# Atmega328p_Custom_Board.net
KiCad netlist of a schematic drawn in EasyEDA
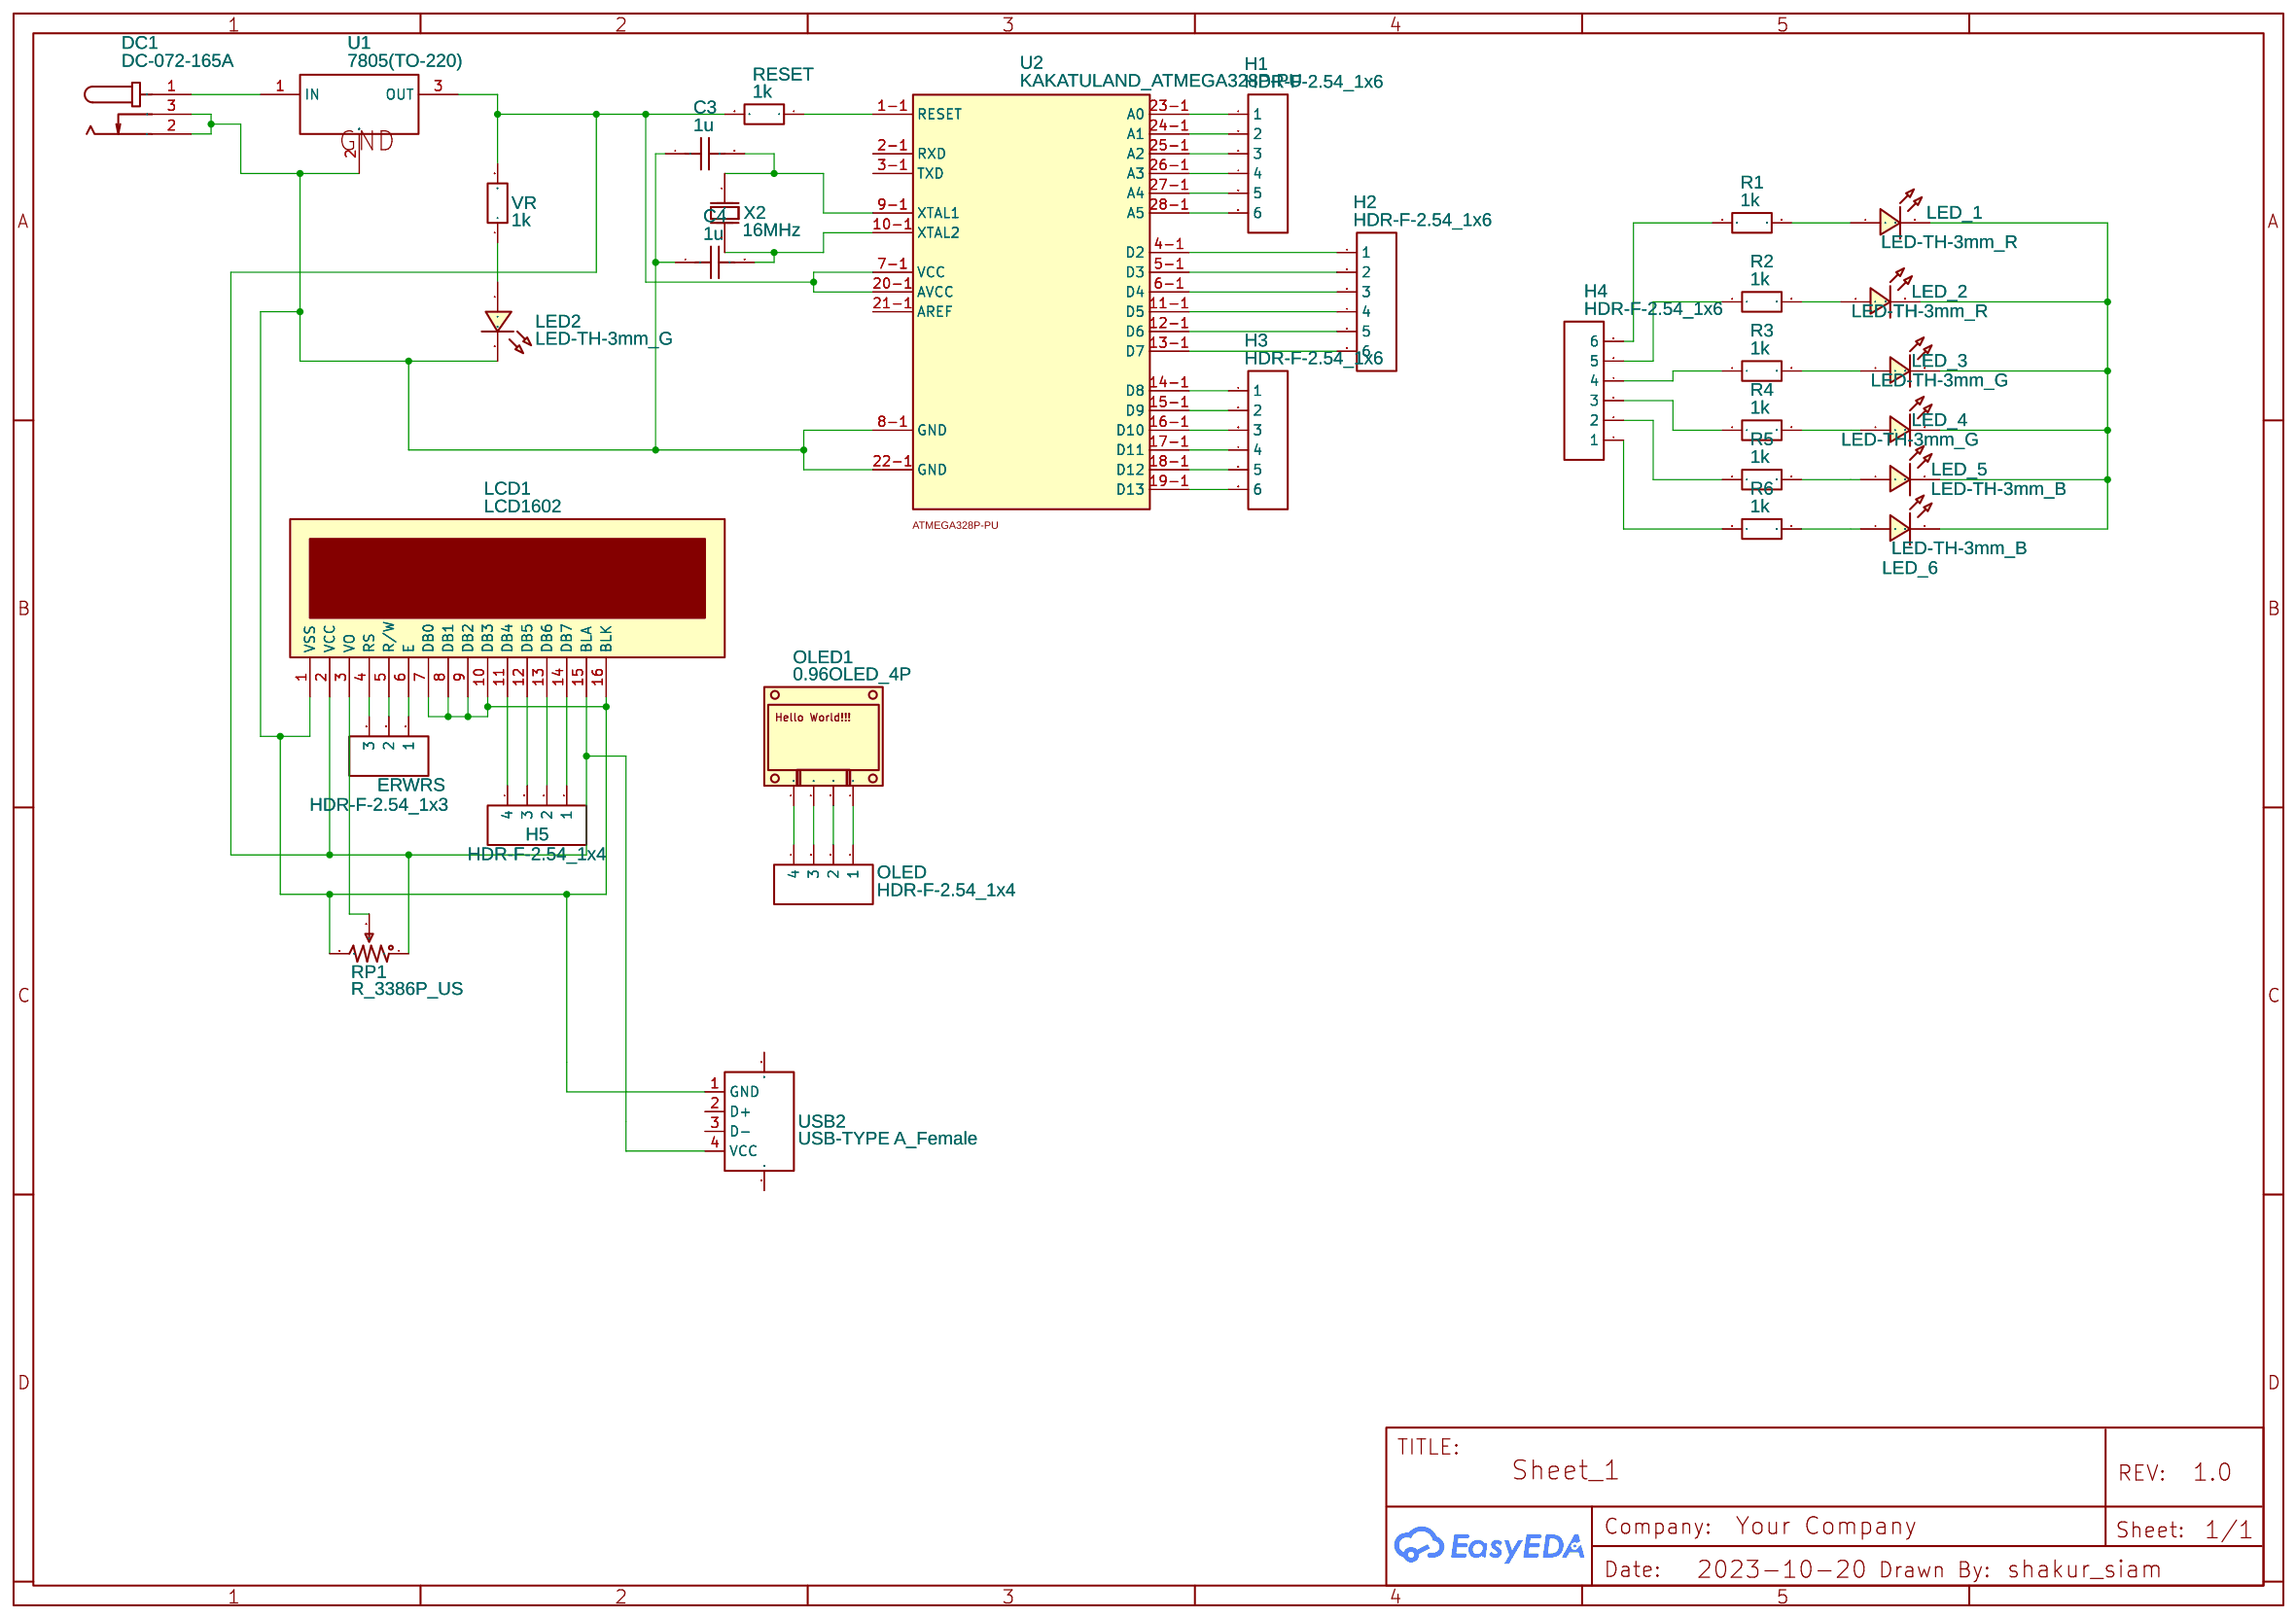
[diagram p0: schematic sheet]

(export (version "E")
  (design (tool "Eeschema 10.0.6"))
  (components
    (comp (ref "C3") (value "1u") (libsource (lib "") (part "C_RAD-0.2_US")))
    (comp (ref "C4") (value "1u") (libsource (lib "") (part "C_RAD-0.2_US")))
    (comp (ref "DC1")
      (value "DC-072-165A")
      (fields (field (name "Manufacturer") "HRO"))
      (libsource (lib "") (part "DC-072-165A"))
    )
    (comp (ref "ERWRS") (value "HDR-F-2.54_1x3") (libsource (lib "") (part "HDR-F-2.54_1x3")))
    (comp (ref "H1") (value "HDR-F-2.54_1x6") (libsource (lib "") (part "HDR-F-2.54_1x6")))
    (comp (ref "H2") (value "HDR-F-2.54_1x6") (libsource (lib "") (part "HDR-F-2.54_1x6")))
    (comp (ref "H3") (value "HDR-F-2.54_1x6") (libsource (lib "") (part "HDR-F-2.54_1x6")))
    (comp (ref "H4") (value "HDR-F-2.54_1x6") (libsource (lib "") (part "HDR-F-2.54_1x6_1")))
    (comp (ref "H5") (value "HDR-F-2.54_1x4") (libsource (lib "") (part "HDR-F-2.54_1x4_1")))
    (comp (ref "LCD1")
      (value "LCD1602")
      (fields
        (field (name "Manufacturer Part") "LCM1602K-NSW-BBW")
        (field (name "Manufacturer") "LONTECH(厦门龙特)")
      )
      (libsource (lib "") (part "LCD1602"))
    )
    (comp (ref "LED2")
      (value "LED-TH-3mm_G")
      (fields
        (field (name "Manufacturer Part") "204-10SYGD/S530-E3")
        (field (name "Manufacturer") "EVERLIGHT(台湾亿光)")
      )
      (libsource (lib "") (part "LED-TH-3mm_G_1"))
    )
    (comp (ref "LED_1")
      (value "LED-TH-3mm_R")
      (fields
        (field (name "Manufacturer Part") "204-10SDRD/S530-A3-L")
        (field (name "Manufacturer") "EVERLIGHT(台湾亿光)")
      )
      (libsource (lib "") (part "LED-TH-3mm_R"))
    )
    (comp (ref "LED_2")
      (value "LED-TH-3mm_R")
      (fields
        (field (name "Manufacturer Part") "204-10SDRD/S530-A3-L")
        (field (name "Manufacturer") "EVERLIGHT(台湾亿光)")
      )
      (libsource (lib "") (part "LED-TH-3mm_R"))
    )
    (comp (ref "LED_3")
      (value "LED-TH-3mm_G")
      (fields
        (field (name "Manufacturer Part") "204-10SYGD/S530-E3")
        (field (name "Manufacturer") "EVERLIGHT(台湾亿光)")
      )
      (libsource (lib "") (part "LED-TH-3mm_G"))
    )
    (comp (ref "LED_4")
      (value "LED-TH-3mm_G")
      (fields
        (field (name "Manufacturer Part") "204-10SYGD/S530-E3")
        (field (name "Manufacturer") "EVERLIGHT(台湾亿光)")
      )
      (libsource (lib "") (part "LED-TH-3mm_G"))
    )
    (comp (ref "LED_5")
      (value "LED-TH-3mm_B")
      (fields
        (field (name "Manufacturer Part") "204-10SUBC/S400-A4")
        (field (name "Manufacturer") "EVERLIGHT(台湾亿光)")
      )
      (libsource (lib "") (part "LED-TH-3mm_B"))
    )
    (comp (ref "LED_6")
      (value "LED-TH-3mm_B")
      (fields
        (field (name "Manufacturer Part") "204-10SUBC/S400-A4")
        (field (name "Manufacturer") "EVERLIGHT(台湾亿光)")
      )
      (libsource (lib "") (part "LED-TH-3mm_B"))
    )
    (comp (ref "OLED") (value "HDR-F-2.54_1x4") (libsource (lib "") (part "HDR-F-2.54_1x4")))
    (comp (ref "OLED1") (value "0.96OLED_4P") (libsource (lib "") (part "0.96OLED_4P")))
    (comp (ref "R1") (value "1k") (libsource (lib "") (part "R_0603_EU")))
    (comp (ref "R2") (value "1k") (libsource (lib "") (part "R_0603_EU")))
    (comp (ref "R3") (value "1k") (libsource (lib "") (part "R_0603_EU")))
    (comp (ref "R4") (value "1k") (libsource (lib "") (part "R_0603_EU")))
    (comp (ref "R5") (value "1k") (libsource (lib "") (part "R_0603_EU")))
    (comp (ref "R6") (value "1k") (libsource (lib "") (part "R_0603_EU")))
    (comp (ref "RESET") (value "1k") (libsource (lib "") (part "R_0603_EU_1")))
    (comp (ref "RP1") (value "R_3386P_US") (libsource (lib "") (part "R_3386P_US")))
    (comp (ref "U1")
      (value "7805(TO-220)")
      (fields
        (field (name "Manufacturer Part") "L7805CV-DG")
        (field (name "Manufacturer") "STMicroelectronics")
      )
      (libsource (lib "") (part "7805(TO-220)"))
    )
    (comp (ref "U2")
      (value "KAKATULAND_ATMEGA328P-PU")
      (libsource (lib "") (part "KAKATULAND_ATMEGA328P-PU"))
    )
    (comp (ref "USB2")
      (value "USB-TYPE A_Female")
      (fields (field (name "Manufacturer") "ValuePro"))
      (libsource (lib "") (part "USB-TYPE A_Female"))
    )
    (comp (ref "VR") (value "1k") (libsource (lib "") (part "R_0603_EU_2")))
    (comp (ref "X2") (value "16MHz") (libsource (lib "") (part "GM-CRYSTAL-16MHz")))
  )
  (nets
    (net (code "1") (name "Net-(H4-Pad1)") (class "Default")
      (node (ref "H4") (pin "1") (pinfunction "1_1") (pintype "input"))
      (node (ref "R6") (pin "1") (pinfunction "1_1") (pintype "unspecified"))
    )
    (net (code "2") (name "Net-(H4-Pad2)") (class "Default")
      (node (ref "H4") (pin "2") (pinfunction "2_2") (pintype "input"))
      (node (ref "R5") (pin "1") (pinfunction "1_1") (pintype "unspecified"))
    )
    (net (code "3") (name "Net-(H4-Pad3)") (class "Default")
      (node (ref "H4") (pin "3") (pinfunction "3_3") (pintype "input"))
      (node (ref "R4") (pin "1") (pinfunction "1_1") (pintype "unspecified"))
    )
    (net (code "4") (name "Net-(H4-Pad4)") (class "Default")
      (node (ref "H4") (pin "4") (pinfunction "4_4") (pintype "input"))
      (node (ref "R3") (pin "1") (pinfunction "1_1") (pintype "unspecified"))
    )
    (net (code "5") (name "Net-(H4-Pad5)") (class "Default")
      (node (ref "H4") (pin "5") (pinfunction "5_5") (pintype "input"))
      (node (ref "R2") (pin "1") (pinfunction "1_1") (pintype "unspecified"))
    )
    (net (code "6") (name "Net-(H4-Pad6)") (class "Default")
      (node (ref "H4") (pin "6") (pinfunction "6_6") (pintype "input"))
      (node (ref "R1") (pin "1") (pinfunction "1_1") (pintype "unspecified"))
    )
    (net (code "7") (name "Net-(LCD1-BLA)") (class "Default")
      (node (ref "LCD1") (pin "15") (pinfunction "BLA_15") (pintype "unspecified"))
      (node (ref "LCD1") (pin "2") (pinfunction "VCC_2") (pintype "unspecified"))
      (node (ref "RESET") (pin "2") (pinfunction "2_2") (pintype "unspecified"))
      (node (ref "RP1") (pin "1") (pinfunction "1_1") (pintype "unspecified"))
      (node (ref "U1") (pin "3") (pinfunction "OUT_3") (pintype "passive"))
      (node (ref "U2") (pin "20-1") (pinfunction "AVCC_20-1") (pintype "passive"))
      (node (ref "U2") (pin "7-1") (pinfunction "VCC_7-1") (pintype "passive"))
      (node (ref "USB2") (pin "4") (pinfunction "VCC_4") (pintype "input"))
      (node (ref "VR") (pin "2") (pinfunction "2_2") (pintype "unspecified"))
    )
    (net (code "8") (name "Net-(LCD1-BLK)") (class "Default")
      (node (ref "C3") (pin "1") (pinfunction "1_1") (pintype "unspecified"))
      (node (ref "C4") (pin "1") (pinfunction "1_1") (pintype "unspecified"))
      (node (ref "DC1") (pin "2") (pinfunction "2_2") (pintype "unspecified"))
      (node (ref "DC1") (pin "3") (pinfunction "3_3") (pintype "unspecified"))
      (node (ref "LCD1") (pin "1") (pinfunction "VSS_1") (pintype "unspecified"))
      (node (ref "LCD1") (pin "10") (pinfunction "DB3_10") (pintype "unspecified"))
      (node (ref "LCD1") (pin "16") (pinfunction "BLK_16") (pintype "unspecified"))
      (node (ref "LCD1") (pin "7") (pinfunction "DB0_7") (pintype "unspecified"))
      (node (ref "LCD1") (pin "8") (pinfunction "DB1_8") (pintype "unspecified"))
      (node (ref "LCD1") (pin "9") (pinfunction "DB2_9") (pintype "unspecified"))
      (node (ref "LED2") (pin "2") (pinfunction "2_2") (pintype "unspecified"))
      (node (ref "RP1") (pin "3") (pinfunction "3_3") (pintype "unspecified"))
      (node (ref "U1") (pin "2") (pinfunction "GND_2") (pintype "passive"))
      (node (ref "U2") (pin "22-1") (pinfunction "GND_22-1") (pintype "passive"))
      (node (ref "U2") (pin "8-1") (pinfunction "GND_8-1") (pintype "passive"))
      (node (ref "USB2") (pin "1") (pinfunction "GND_1") (pintype "input"))
    )
    (net (code "9") (name "Net-(LCD1-DB4)") (class "Default")
      (node (ref "H5") (pin "4") (pinfunction "4_4") (pintype "unspecified"))
      (node (ref "LCD1") (pin "11") (pinfunction "DB4_11") (pintype "unspecified"))
    )
    (net (code "10") (name "Net-(LCD1-DB5)") (class "Default")
      (node (ref "H5") (pin "3") (pinfunction "3_3") (pintype "unspecified"))
      (node (ref "LCD1") (pin "12") (pinfunction "DB5_12") (pintype "unspecified"))
    )
    (net (code "11") (name "Net-(LCD1-DB6)") (class "Default")
      (node (ref "H5") (pin "2") (pinfunction "2_2") (pintype "unspecified"))
      (node (ref "LCD1") (pin "13") (pinfunction "DB6_13") (pintype "unspecified"))
    )
    (net (code "12") (name "Net-(LCD1-DB7)") (class "Default")
      (node (ref "H5") (pin "1") (pinfunction "1_1") (pintype "unspecified"))
      (node (ref "LCD1") (pin "14") (pinfunction "DB7_14") (pintype "unspecified"))
    )
    (net (code "13") (name "Net-(LCD1-E)") (class "Default")
      (node (ref "ERWRS") (pin "1") (pinfunction "1_1") (pintype "input"))
      (node (ref "LCD1") (pin "6") (pinfunction "E_6") (pintype "unspecified"))
    )
    (net (code "14") (name "Net-(LCD1-RS)") (class "Default")
      (node (ref "ERWRS") (pin "3") (pinfunction "3_3") (pintype "input"))
      (node (ref "LCD1") (pin "4") (pinfunction "RS_4") (pintype "unspecified"))
    )
    (net (code "15") (name "Net-(LCD1-R{slash}W)") (class "Default")
      (node (ref "ERWRS") (pin "2") (pinfunction "2_2") (pintype "input"))
      (node (ref "LCD1") (pin "5") (pinfunction "R/W_5") (pintype "unspecified"))
    )
    (net (code "16") (name "Net-(LCD1-VO)") (class "Default")
      (node (ref "LCD1") (pin "3") (pinfunction "VO_3") (pintype "unspecified"))
      (node (ref "RP1") (pin "2") (pinfunction "2_2") (pintype "unspecified"))
    )
    (net (code "17") (name "Net-(LED2-Pad1)") (class "Default")
      (node (ref "LED2") (pin "1") (pinfunction "1_1") (pintype "unspecified"))
      (node (ref "VR") (pin "1") (pinfunction "1_1") (pintype "unspecified"))
    )
    (net (code "18") (name "Net-(LED_1-Pad1)") (class "Default")
      (node (ref "LED_1") (pin "1") (pinfunction "1_1") (pintype "unspecified"))
      (node (ref "R1") (pin "2") (pinfunction "2_2") (pintype "unspecified"))
    )
    (net (code "19") (name "Net-(LED_1-Pad2)") (class "Default")
      (node (ref "LED_1") (pin "2") (pinfunction "2_2") (pintype "unspecified"))
      (node (ref "LED_2") (pin "2") (pinfunction "2_2") (pintype "unspecified"))
      (node (ref "LED_3") (pin "2") (pinfunction "2_2") (pintype "unspecified"))
      (node (ref "LED_4") (pin "2") (pinfunction "2_2") (pintype "unspecified"))
      (node (ref "LED_5") (pin "2") (pinfunction "2_2") (pintype "unspecified"))
      (node (ref "LED_6") (pin "2") (pinfunction "2_2") (pintype "unspecified"))
    )
    (net (code "20") (name "Net-(LED_2-Pad1)") (class "Default")
      (node (ref "LED_2") (pin "1") (pinfunction "1_1") (pintype "unspecified"))
      (node (ref "R2") (pin "2") (pinfunction "2_2") (pintype "unspecified"))
    )
    (net (code "21") (name "Net-(LED_3-Pad1)") (class "Default")
      (node (ref "LED_3") (pin "1") (pinfunction "1_1") (pintype "unspecified"))
      (node (ref "R3") (pin "2") (pinfunction "2_2") (pintype "unspecified"))
    )
    (net (code "22") (name "Net-(LED_4-Pad1)") (class "Default")
      (node (ref "LED_4") (pin "1") (pinfunction "1_1") (pintype "unspecified"))
      (node (ref "R4") (pin "2") (pinfunction "2_2") (pintype "unspecified"))
    )
    (net (code "23") (name "Net-(LED_5-Pad1)") (class "Default")
      (node (ref "LED_5") (pin "1") (pinfunction "1_1") (pintype "unspecified"))
      (node (ref "R5") (pin "2") (pinfunction "2_2") (pintype "unspecified"))
    )
    (net (code "24") (name "Net-(LED_6-Pad1)") (class "Default")
      (node (ref "LED_6") (pin "1") (pinfunction "1_1") (pintype "unspecified"))
      (node (ref "R6") (pin "2") (pinfunction "2_2") (pintype "unspecified"))
    )
    (net (code "25") (name "Net-(OLED-Pad1)") (class "Default")
      (node (ref "OLED") (pin "1") (pinfunction "1_1") (pintype "unspecified"))
      (node (ref "OLED1") (pin "4") (pinfunction "4_4") (pintype "unspecified"))
    )
    (net (code "26") (name "Net-(OLED-Pad2)") (class "Default")
      (node (ref "OLED") (pin "2") (pinfunction "2_2") (pintype "unspecified"))
      (node (ref "OLED1") (pin "3") (pinfunction "3_3") (pintype "unspecified"))
    )
    (net (code "27") (name "Net-(OLED-Pad3)") (class "Default")
      (node (ref "OLED") (pin "3") (pinfunction "3_3") (pintype "unspecified"))
      (node (ref "OLED1") (pin "2") (pinfunction "2_2") (pintype "unspecified"))
    )
    (net (code "28") (name "Net-(OLED-Pad4)") (class "Default")
      (node (ref "OLED") (pin "4") (pinfunction "4_4") (pintype "unspecified"))
      (node (ref "OLED1") (pin "1") (pinfunction "1_1") (pintype "unspecified"))
    )
    (net (code "29") (name "Net-(U1-IN)") (class "Default")
      (node (ref "DC1") (pin "1") (pinfunction "1_1") (pintype "unspecified"))
      (node (ref "U1") (pin "1") (pinfunction "IN_1") (pintype "passive"))
    )
    (net (code "30") (name "Net-(U2-A0)") (class "Default")
      (node (ref "H1") (pin "1") (pinfunction "1_1") (pintype "input"))
      (node (ref "U2") (pin "23-1") (pinfunction "A0_23-1") (pintype "bidirectional"))
    )
    (net (code "31") (name "Net-(U2-A1)") (class "Default")
      (node (ref "H1") (pin "2") (pinfunction "2_2") (pintype "input"))
      (node (ref "U2") (pin "24-1") (pinfunction "A1_24-1") (pintype "bidirectional"))
    )
    (net (code "32") (name "Net-(U2-A2)") (class "Default")
      (node (ref "H1") (pin "3") (pinfunction "3_3") (pintype "input"))
      (node (ref "U2") (pin "25-1") (pinfunction "A2_25-1") (pintype "bidirectional"))
    )
    (net (code "33") (name "Net-(U2-A3)") (class "Default")
      (node (ref "H1") (pin "4") (pinfunction "4_4") (pintype "input"))
      (node (ref "U2") (pin "26-1") (pinfunction "A3_26-1") (pintype "bidirectional"))
    )
    (net (code "34") (name "Net-(U2-A4)") (class "Default")
      (node (ref "H1") (pin "5") (pinfunction "5_5") (pintype "input"))
      (node (ref "U2") (pin "27-1") (pinfunction "A4_27-1") (pintype "bidirectional"))
    )
    (net (code "35") (name "Net-(U2-A5)") (class "Default")
      (node (ref "H1") (pin "6") (pinfunction "6_6") (pintype "input"))
      (node (ref "U2") (pin "28-1") (pinfunction "A5_28-1") (pintype "bidirectional"))
    )
    (net (code "36") (name "Net-(U2-D2)") (class "Default")
      (node (ref "H2") (pin "1") (pinfunction "1_1") (pintype "input"))
      (node (ref "U2") (pin "4-1") (pinfunction "D2_4-1") (pintype "bidirectional"))
    )
    (net (code "37") (name "Net-(U2-D3)") (class "Default")
      (node (ref "H2") (pin "2") (pinfunction "2_2") (pintype "input"))
      (node (ref "U2") (pin "5-1") (pinfunction "D3_5-1") (pintype "bidirectional"))
    )
    (net (code "38") (name "Net-(U2-D4)") (class "Default")
      (node (ref "H2") (pin "3") (pinfunction "3_3") (pintype "input"))
      (node (ref "U2") (pin "6-1") (pinfunction "D4_6-1") (pintype "bidirectional"))
    )
    (net (code "39") (name "Net-(U2-D5)") (class "Default")
      (node (ref "H2") (pin "4") (pinfunction "4_4") (pintype "input"))
      (node (ref "U2") (pin "11-1") (pinfunction "D5_11-1") (pintype "bidirectional"))
    )
    (net (code "40") (name "Net-(U2-D6)") (class "Default")
      (node (ref "H2") (pin "5") (pinfunction "5_5") (pintype "input"))
      (node (ref "U2") (pin "12-1") (pinfunction "D6_12-1") (pintype "bidirectional"))
    )
    (net (code "41") (name "Net-(U2-D7)") (class "Default")
      (node (ref "H2") (pin "6") (pinfunction "6_6") (pintype "input"))
      (node (ref "U2") (pin "13-1") (pinfunction "D7_13-1") (pintype "bidirectional"))
    )
    (net (code "42") (name "Net-(U2-D8)") (class "Default")
      (node (ref "H3") (pin "1") (pinfunction "1_1") (pintype "input"))
      (node (ref "U2") (pin "14-1") (pinfunction "D8_14-1") (pintype "bidirectional"))
    )
    (net (code "43") (name "Net-(U2-D9)") (class "Default")
      (node (ref "H3") (pin "2") (pinfunction "2_2") (pintype "input"))
      (node (ref "U2") (pin "15-1") (pinfunction "D9_15-1") (pintype "bidirectional"))
    )
    (net (code "44") (name "Net-(U2-D10)") (class "Default")
      (node (ref "H3") (pin "3") (pinfunction "3_3") (pintype "input"))
      (node (ref "U2") (pin "16-1") (pinfunction "D10_16-1") (pintype "bidirectional"))
    )
    (net (code "45") (name "Net-(U2-D11)") (class "Default")
      (node (ref "H3") (pin "4") (pinfunction "4_4") (pintype "input"))
      (node (ref "U2") (pin "17-1") (pinfunction "D11_17-1") (pintype "bidirectional"))
    )
    (net (code "46") (name "Net-(U2-D12)") (class "Default")
      (node (ref "H3") (pin "5") (pinfunction "5_5") (pintype "input"))
      (node (ref "U2") (pin "18-1") (pinfunction "D12_18-1") (pintype "bidirectional"))
    )
    (net (code "47") (name "Net-(U2-D13)") (class "Default")
      (node (ref "H3") (pin "6") (pinfunction "6_6") (pintype "input"))
      (node (ref "U2") (pin "19-1") (pinfunction "D13_19-1") (pintype "bidirectional"))
    )
    (net (code "48") (name "Net-(U2-RESET)") (class "Default")
      (node (ref "RESET") (pin "1") (pinfunction "1_1") (pintype "unspecified"))
      (node (ref "U2") (pin "1-1") (pinfunction "RESET_1-1") (pintype "bidirectional"))
    )
    (net (code "49") (name "Net-(U2-XTAL1)") (class "Default")
      (node (ref "C3") (pin "2") (pinfunction "2_2") (pintype "unspecified"))
      (node (ref "U2") (pin "9-1") (pinfunction "XTAL1_9-1") (pintype "bidirectional"))
      (node (ref "X2") (pin "1") (pinfunction "1_1") (pintype "unspecified"))
    )
    (net (code "50") (name "Net-(U2-XTAL2)") (class "Default")
      (node (ref "C4") (pin "2") (pinfunction "2_2") (pintype "unspecified"))
      (node (ref "U2") (pin "10-1") (pinfunction "XTAL2_10-1") (pintype "bidirectional"))
      (node (ref "X2") (pin "2") (pinfunction "2_2") (pintype "unspecified"))
    )
    (net (code "51") (name "unconnected-(U2-AREF-Pad21-1)") (class "Default")
      (node (ref "U2") (pin "21-1") (pinfunction "AREF_21-1") (pintype "passive"))
    )
    (net (code "52") (name "unconnected-(U2-RXD-Pad2-1)") (class "Default")
      (node (ref "U2") (pin "2-1") (pinfunction "RXD_2-1") (pintype "bidirectional"))
    )
    (net (code "53") (name "unconnected-(U2-TXD-Pad3-1)") (class "Default")
      (node (ref "U2") (pin "3-1") (pinfunction "TXD_3-1") (pintype "bidirectional"))
    )
    (net (code "54") (name "unconnected-(USB2-D+-Pad2)") (class "Default")
      (node (ref "USB2") (pin "2") (pinfunction "D+_2") (pintype "input"))
    )
    (net (code "55") (name "unconnected-(USB2-D--Pad3)") (class "Default")
      (node (ref "USB2") (pin "3") (pinfunction "D-_3") (pintype "input"))
    )
    (net (code "56") (name "unconnected-(USB2-Pad5)") (class "Default")
      (node (ref "USB2") (pin "5") (pinfunction "5_5") (pintype "unspecified"))
    )
    (net (code "57") (name "unconnected-(USB2-Pad6)") (class "Default")
      (node (ref "USB2") (pin "6") (pinfunction "6_6") (pintype "unspecified"))
    )
  )
)
